# vco1_components.net
KiCad netlist of a schematic drawn in EAGLE
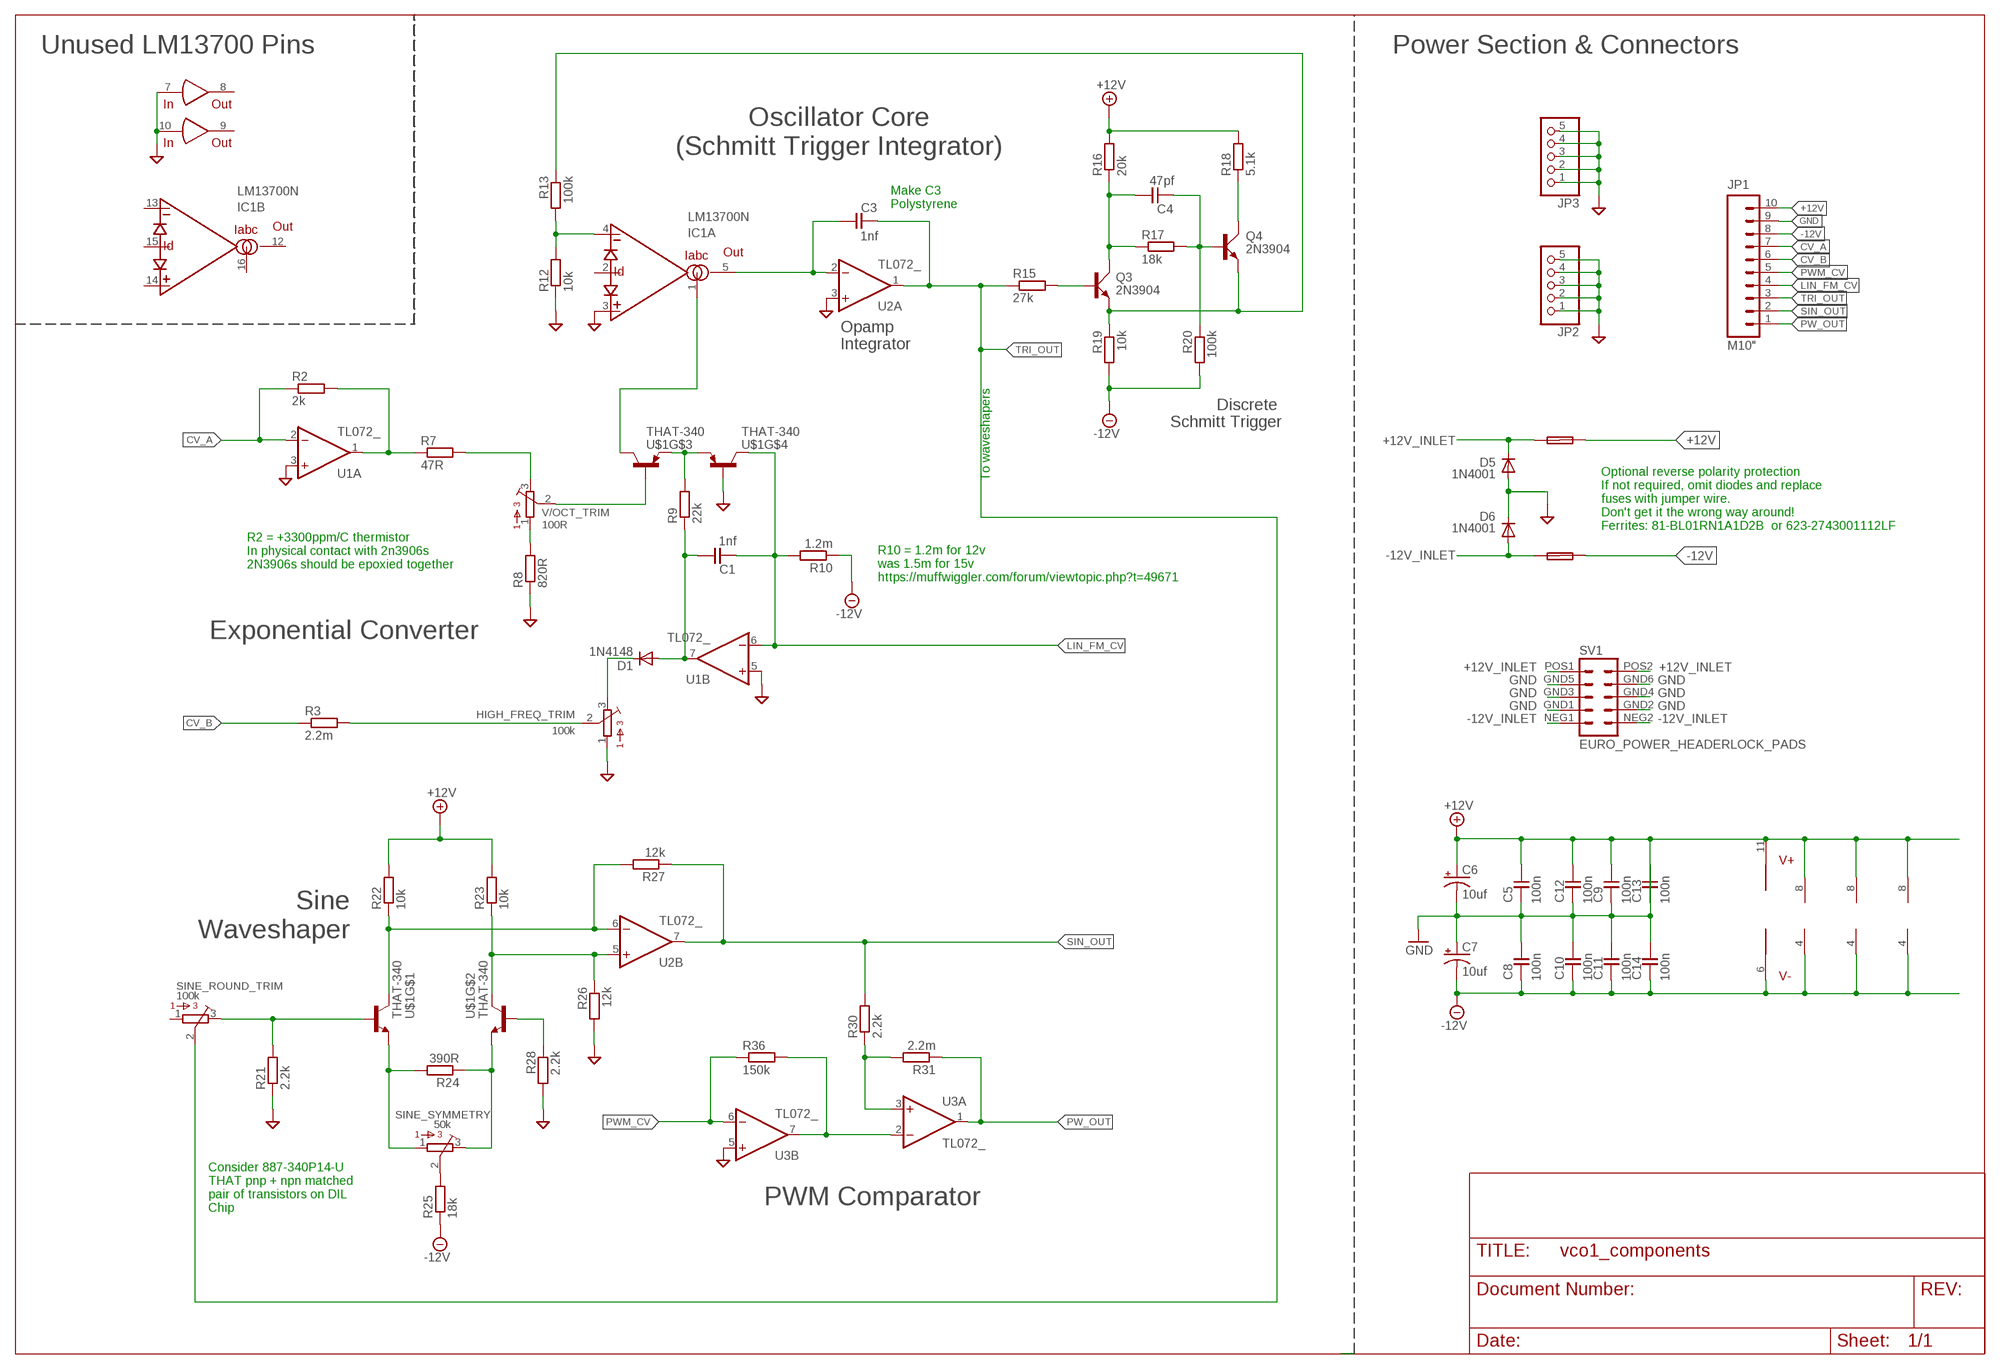
[diagram p0: schematic, sheet 1]

(export (version "E")
  (design (tool "Eeschema 10.0.6"))
  (components
    (comp (ref "C1")
      (value "1nf")
      (footprint "eagle-import:C050-024X044")
      (libsource (lib "eagle-import") (part "C-EU050-024X044"))
    )
    (comp (ref "C3")
      (value "1nf")
      (footprint "eagle-import:C050-024X044")
      (libsource (lib "eagle-import") (part "C-EU050-024X044"))
    )
    (comp (ref "C4")
      (value "47pf")
      (footprint "eagle-import:C050-024X044")
      (libsource (lib "eagle-import") (part "C-EU050-024X044"))
    )
    (comp (ref "C5")
      (value "100n")
      (footprint "eagle-import:C050-024X044")
      (libsource (lib "eagle-import") (part "C-EU050-024X044"))
    )
    (comp (ref "C6")
      (value "10uf")
      (footprint "eagle-import:CPOL-RADIAL-10UF-25V")
      (libsource (lib "eagle-import") (part "CAP_POLPTH2"))
    )
    (comp (ref "C7")
      (value "10uf")
      (footprint "eagle-import:CPOL-RADIAL-10UF-25V")
      (libsource (lib "eagle-import") (part "CAP_POLPTH2"))
    )
    (comp (ref "C8")
      (value "100n")
      (footprint "eagle-import:C050-024X044")
      (libsource (lib "eagle-import") (part "C-EU050-024X044"))
    )
    (comp (ref "C9")
      (value "100n")
      (footprint "eagle-import:C050-024X044")
      (libsource (lib "eagle-import") (part "C-EU050-024X044"))
    )
    (comp (ref "C10")
      (value "100n")
      (footprint "eagle-import:C050-024X044")
      (libsource (lib "eagle-import") (part "C-EU050-024X044"))
    )
    (comp (ref "C11")
      (value "100n")
      (footprint "eagle-import:C050-024X044")
      (libsource (lib "eagle-import") (part "C-EU050-024X044"))
    )
    (comp (ref "C12")
      (value "100n")
      (footprint "eagle-import:C050-024X044")
      (libsource (lib "eagle-import") (part "C-EU050-024X044"))
    )
    (comp (ref "C13")
      (value "100n")
      (footprint "eagle-import:C050-024X044")
      (libsource (lib "eagle-import") (part "C-EU050-024X044"))
    )
    (comp (ref "C14")
      (value "100n")
      (footprint "eagle-import:C050-024X044")
      (libsource (lib "eagle-import") (part "C-EU050-024X044"))
    )
    (comp (ref "D1")
      (value "1N4148")
      (footprint "eagle-import:DO35-7")
      (libsource (lib "eagle-import") (part "SMALL_DIODEDO35-7"))
    )
    (comp (ref "D5")
      (value "1N4001")
      (footprint "eagle-import:DO41-10")
      (libsource (lib "eagle-import") (part "1N4004"))
    )
    (comp (ref "D6")
      (value "1N4001")
      (footprint "eagle-import:DO41-10")
      (libsource (lib "eagle-import") (part "1N4004"))
    )
    (comp (ref "F1")
      (value "FUSE")
      (footprint "eagle-import:C050H075X075")
      (libsource (lib "eagle-import") (part "PTC_FUSEPOLY_FUSE"))
    )
    (comp (ref "F2")
      (value "FUSE")
      (footprint "eagle-import:C050H075X075")
      (libsource (lib "eagle-import") (part "PTC_FUSEPOLY_FUSE"))
    )
    (comp (ref "HIGH_FREQ_TRIM")
      (value "100k")
      (footprint "eagle-import:BOURNS_3362P_TRIMMER")
      (libsource (lib "eagle-import") (part "BOURNS_3362P_TRIMMERP"))
    )
    (comp (ref "IC1")
      (value "LM13700N")
      (footprint "eagle-import:DIL16")
      (libsource (lib "eagle-import") (part "LM13700N"))
    )
    (comp (ref "JP1")
      (value "M10\"")
      (footprint "eagle-import:1X10")
      (libsource (lib "eagle-import") (part "M10{dblquote}"))
    )
    (comp (ref "JP2")
      (value "PINHD-1X55X2MM")
      (footprint "eagle-import:1_05X2MM")
      (libsource (lib "eagle-import") (part "PINHD-1X55X2MM"))
    )
    (comp (ref "JP3")
      (value "PINHD-1X55X2MM")
      (footprint "eagle-import:1_05X2MM")
      (libsource (lib "eagle-import") (part "PINHD-1X55X2MM"))
    )
    (comp (ref "Q3")
      (value "2N3904")
      (footprint "eagle-import:TO92D")
      (libsource (lib "eagle-import") (part "2N3904"))
    )
    (comp (ref "Q4")
      (value "2N3904")
      (footprint "eagle-import:TO92D")
      (libsource (lib "eagle-import") (part "2N3904"))
    )
    (comp (ref "R2")
      (value "2k")
      (footprint "eagle-import:7MM_RESISTOR")
      (libsource (lib "eagle-import") (part "RESISTOR7MM"))
    )
    (comp (ref "R3")
      (value "2.2m")
      (footprint "eagle-import:7MM_RESISTOR")
      (libsource (lib "eagle-import") (part "RESISTOR7MM"))
    )
    (comp (ref "R7")
      (value "47R")
      (footprint "eagle-import:7MM_RESISTOR")
      (libsource (lib "eagle-import") (part "RESISTOR7MM"))
    )
    (comp (ref "R8")
      (value "820R")
      (footprint "eagle-import:7MM_RESISTOR")
      (libsource (lib "eagle-import") (part "RESISTOR7MM"))
    )
    (comp (ref "R9")
      (value "22k")
      (footprint "eagle-import:7MM_RESISTOR")
      (libsource (lib "eagle-import") (part "RESISTOR7MM"))
    )
    (comp (ref "R10")
      (value "1.2m")
      (footprint "eagle-import:7MM_RESISTOR")
      (libsource (lib "eagle-import") (part "RESISTOR7MM"))
    )
    (comp (ref "R12")
      (value "10k")
      (footprint "eagle-import:7MM_RESISTOR")
      (libsource (lib "eagle-import") (part "RESISTOR7MM"))
    )
    (comp (ref "R13")
      (value "100k")
      (footprint "eagle-import:7MM_RESISTOR")
      (libsource (lib "eagle-import") (part "RESISTOR7MM"))
    )
    (comp (ref "R15")
      (value "27k")
      (footprint "eagle-import:7MM_RESISTOR")
      (libsource (lib "eagle-import") (part "RESISTOR7MM"))
    )
    (comp (ref "R16")
      (value "20k")
      (footprint "eagle-import:7MM_RESISTOR")
      (libsource (lib "eagle-import") (part "RESISTOR7MM"))
    )
    (comp (ref "R17")
      (value "18k")
      (footprint "eagle-import:7MM_RESISTOR")
      (libsource (lib "eagle-import") (part "RESISTOR7MM"))
    )
    (comp (ref "R18")
      (value "5.1k")
      (footprint "eagle-import:7MM_RESISTOR")
      (libsource (lib "eagle-import") (part "RESISTOR7MM"))
    )
    (comp (ref "R19")
      (value "10k")
      (footprint "eagle-import:7MM_RESISTOR")
      (libsource (lib "eagle-import") (part "RESISTOR7MM"))
    )
    (comp (ref "R20")
      (value "100k")
      (footprint "eagle-import:7MM_RESISTOR")
      (libsource (lib "eagle-import") (part "RESISTOR7MM"))
    )
    (comp (ref "R21")
      (value "2.2k")
      (footprint "eagle-import:7MM_RESISTOR")
      (libsource (lib "eagle-import") (part "RESISTOR7MM"))
    )
    (comp (ref "R22")
      (value "10k")
      (footprint "eagle-import:7MM_RESISTOR")
      (libsource (lib "eagle-import") (part "RESISTOR7MM"))
    )
    (comp (ref "R23")
      (value "10k")
      (footprint "eagle-import:7MM_RESISTOR")
      (libsource (lib "eagle-import") (part "RESISTOR7MM"))
    )
    (comp (ref "R24")
      (value "390R")
      (footprint "eagle-import:7MM_RESISTOR")
      (libsource (lib "eagle-import") (part "RESISTOR7MM"))
    )
    (comp (ref "R25")
      (value "18k")
      (footprint "eagle-import:7MM_RESISTOR")
      (libsource (lib "eagle-import") (part "RESISTOR7MM"))
    )
    (comp (ref "R26")
      (value "12k")
      (footprint "eagle-import:7MM_RESISTOR")
      (libsource (lib "eagle-import") (part "RESISTOR7MM"))
    )
    (comp (ref "R27")
      (value "12k")
      (footprint "eagle-import:7MM_RESISTOR")
      (libsource (lib "eagle-import") (part "RESISTOR7MM"))
    )
    (comp (ref "R28")
      (value "2.2k")
      (footprint "eagle-import:7MM_RESISTOR")
      (libsource (lib "eagle-import") (part "RESISTOR7MM"))
    )
    (comp (ref "R30")
      (value "2.2k")
      (footprint "eagle-import:7MM_RESISTOR")
      (libsource (lib "eagle-import") (part "RESISTOR7MM"))
    )
    (comp (ref "R31")
      (value "2.2m")
      (footprint "eagle-import:7MM_RESISTOR")
      (libsource (lib "eagle-import") (part "RESISTOR7MM"))
    )
    (comp (ref "R36")
      (value "150k")
      (footprint "eagle-import:7MM_RESISTOR")
      (libsource (lib "eagle-import") (part "RESISTOR7MM"))
    )
    (comp (ref "SINE_ROUND_TRIM")
      (value "100k")
      (footprint "eagle-import:BOURNS_3362P_TRIMMER")
      (libsource (lib "eagle-import") (part "BOURNS_3362P_TRIMMERP"))
    )
    (comp (ref "SINE_SYMMETRY")
      (value "50k")
      (footprint "eagle-import:BOURNS_3362P_TRIMMER")
      (libsource (lib "eagle-import") (part "BOURNS_3362P_TRIMMERP"))
    )
    (comp (ref "SV1")
      (value "EURO_POWER_HEADERLOCK_PADS")
      (footprint "eagle-import:EURO_PWR_HEADER_LOCK")
      (libsource (lib "eagle-import") (part "EURO_POWER_HEADERLOCK_PADS"))
    )
    (comp (ref "U$1")
      (value "THAT-340")
      (footprint "eagle-import:DIL14")
      (libsource (lib "eagle-import") (part "THAT-340THRUHOLE"))
    )
    (comp (ref "U1")
      (value "TL072_")
      (footprint "eagle-import:DIL08")
      (libsource (lib "eagle-import") (part "TL072_"))
    )
    (comp (ref "U2")
      (value "TL072_")
      (footprint "eagle-import:DIL08")
      (libsource (lib "eagle-import") (part "TL072_"))
    )
    (comp (ref "U3")
      (value "TL072_")
      (footprint "eagle-import:DIL08")
      (libsource (lib "eagle-import") (part "TL072_"))
    )
    (comp (ref "V/OCT_TRIM")
      (value "100R")
      (footprint "eagle-import:BOURNS_3362P_TRIMMER")
      (libsource (lib "eagle-import") (part "BOURNS_3362P_TRIMMERP"))
    )
  )
  (nets
    (net (code "1") (name "+12V") (class "Default")
      (node (ref "C12") (pin "1") (pinfunction "1_1") (pintype "passive"))
      (node (ref "C13") (pin "2") (pinfunction "2_2") (pintype "passive"))
      (node (ref "C5") (pin "1") (pinfunction "1_1") (pintype "passive"))
      (node (ref "C6") (pin "1") (pinfunction "+_1") (pintype "passive"))
      (node (ref "C9") (pin "1") (pinfunction "1_1") (pintype "passive"))
      (node (ref "F1") (pin "2") (pinfunction "P$2_2") (pintype "bidirectional"))
      (node (ref "IC1") (pin "11") (pinfunction "V+_11") (pintype "bidirectional"))
      (node (ref "JP1") (pin "10") (pinfunction "10_10") (pintype "passive"))
      (node (ref "R16") (pin "2") (pinfunction "2_2") (pintype "passive"))
      (node (ref "R18") (pin "2") (pinfunction "2_2") (pintype "passive"))
      (node (ref "R22") (pin "2") (pinfunction "2_2") (pintype "passive"))
      (node (ref "R23") (pin "2") (pinfunction "2_2") (pintype "passive"))
      (node (ref "U1") (pin "8") (pinfunction "V+_8") (pintype "power_in"))
      (node (ref "U2") (pin "8") (pinfunction "V+_8") (pintype "power_in"))
      (node (ref "U3") (pin "8") (pinfunction "V+_8") (pintype "power_in"))
    )
    (net (code "2") (name "-12V") (class "Default")
      (node (ref "C10") (pin "2") (pinfunction "2_2") (pintype "passive"))
      (node (ref "C11") (pin "2") (pinfunction "2_2") (pintype "passive"))
      (node (ref "C14") (pin "2") (pinfunction "2_2") (pintype "passive"))
      (node (ref "C7") (pin "2") (pinfunction "-_2") (pintype "passive"))
      (node (ref "C8") (pin "2") (pinfunction "2_2") (pintype "passive"))
      (node (ref "F2") (pin "2") (pinfunction "P$2_2") (pintype "bidirectional"))
      (node (ref "IC1") (pin "6") (pinfunction "V-_6") (pintype "bidirectional"))
      (node (ref "JP1") (pin "8") (pinfunction "8_8") (pintype "passive"))
      (node (ref "R10") (pin "1") (pinfunction "1_1") (pintype "passive"))
      (node (ref "R19") (pin "2") (pinfunction "2_2") (pintype "passive"))
      (node (ref "R20") (pin "2") (pinfunction "2_2") (pintype "passive"))
      (node (ref "R25") (pin "1") (pinfunction "1_1") (pintype "passive"))
      (node (ref "U1") (pin "4") (pinfunction "V-_4") (pintype "power_in"))
      (node (ref "U2") (pin "4") (pinfunction "V-_4") (pintype "power_in"))
      (node (ref "U3") (pin "4") (pinfunction "V-_4") (pintype "power_in"))
    )
    (net (code "3") (name "/+12V_INLET") (class "Default")
      (node (ref "D5") (pin "C") (pinfunction "C_C") (pintype "passive"))
      (node (ref "F1") (pin "1") (pinfunction "P$1_1") (pintype "bidirectional"))
      (node (ref "SV1") (pin "POS1") (pinfunction "10_POS1") (pintype "passive"))
      (node (ref "SV1") (pin "POS2") (pinfunction "9_POS2") (pintype "passive"))
    )
    (net (code "4") (name "/-12V_INLET") (class "Default")
      (node (ref "D6") (pin "A") (pinfunction "A_A") (pintype "passive"))
      (node (ref "F2") (pin "1") (pinfunction "P$1_1") (pintype "bidirectional"))
      (node (ref "SV1") (pin "NEG1") (pinfunction "2_NEG1") (pintype "passive"))
      (node (ref "SV1") (pin "NEG2") (pinfunction "1_NEG2") (pintype "passive"))
    )
    (net (code "5") (name "CV_A") (class "Default")
      (node (ref "JP1") (pin "7") (pinfunction "7_7") (pintype "passive"))
      (node (ref "R2") (pin "1") (pinfunction "1_1") (pintype "passive"))
      (node (ref "U1") (pin "2") (pinfunction "-IN_2") (pintype "input"))
    )
    (net (code "6") (name "CV_B") (class "Default")
      (node (ref "JP1") (pin "6") (pinfunction "6_6") (pintype "passive"))
      (node (ref "R3") (pin "1") (pinfunction "1_1") (pintype "passive"))
    )
    (net (code "7") (name "GND") (class "Default")
      (node (ref "C10") (pin "1") (pinfunction "1_1") (pintype "passive"))
      (node (ref "C11") (pin "1") (pinfunction "1_1") (pintype "passive"))
      (node (ref "C12") (pin "2") (pinfunction "2_2") (pintype "passive"))
      (node (ref "C13") (pin "1") (pinfunction "1_1") (pintype "passive"))
      (node (ref "C14") (pin "1") (pinfunction "1_1") (pintype "passive"))
      (node (ref "C5") (pin "2") (pinfunction "2_2") (pintype "passive"))
      (node (ref "C6") (pin "2") (pinfunction "-_2") (pintype "passive"))
      (node (ref "C7") (pin "1") (pinfunction "+_1") (pintype "passive"))
      (node (ref "C8") (pin "1") (pinfunction "1_1") (pintype "passive"))
      (node (ref "C9") (pin "2") (pinfunction "2_2") (pintype "passive"))
      (node (ref "D5") (pin "A") (pinfunction "A_A") (pintype "passive"))
      (node (ref "D6") (pin "C") (pinfunction "C_C") (pintype "passive"))
      (node (ref "HIGH_FREQ_TRIM") (pin "1") (pinfunction "1_1") (pintype "passive"))
      (node (ref "IC1") (pin "10") (pinfunction "IN_10") (pintype "bidirectional"))
      (node (ref "IC1") (pin "3") (pinfunction "+IN_3") (pintype "bidirectional"))
      (node (ref "IC1") (pin "7") (pinfunction "IN_7") (pintype "bidirectional"))
      (node (ref "JP1") (pin "9") (pinfunction "9_9") (pintype "passive"))
      (node (ref "JP2") (pin "1") (pinfunction "1_1") (pintype "passive"))
      (node (ref "JP2") (pin "2") (pinfunction "2_2") (pintype "passive"))
      (node (ref "JP2") (pin "3") (pinfunction "3_3") (pintype "passive"))
      (node (ref "JP2") (pin "4") (pinfunction "4_4") (pintype "passive"))
      (node (ref "JP2") (pin "5") (pinfunction "5_5") (pintype "passive"))
      (node (ref "JP3") (pin "1") (pinfunction "1_1") (pintype "passive"))
      (node (ref "JP3") (pin "2") (pinfunction "2_2") (pintype "passive"))
      (node (ref "JP3") (pin "3") (pinfunction "3_3") (pintype "passive"))
      (node (ref "JP3") (pin "4") (pinfunction "4_4") (pintype "passive"))
      (node (ref "JP3") (pin "5") (pinfunction "5_5") (pintype "passive"))
      (node (ref "R12") (pin "1") (pinfunction "1_1") (pintype "passive"))
      (node (ref "R21") (pin "1") (pinfunction "1_1") (pintype "passive"))
      (node (ref "R26") (pin "2") (pinfunction "2_2") (pintype "passive"))
      (node (ref "R28") (pin "2") (pinfunction "2_2") (pintype "passive"))
      (node (ref "R8") (pin "1") (pinfunction "1_1") (pintype "passive"))
      (node (ref "SV1") (pin "GND1") (pinfunction "4_GND1") (pintype "passive"))
      (node (ref "SV1") (pin "GND2") (pinfunction "3_GND2") (pintype "passive"))
      (node (ref "SV1") (pin "GND3") (pinfunction "6_GND3") (pintype "passive"))
      (node (ref "SV1") (pin "GND4") (pinfunction "5_GND4") (pintype "passive"))
      (node (ref "SV1") (pin "GND5") (pinfunction "8_GND5") (pintype "passive"))
      (node (ref "SV1") (pin "GND6") (pinfunction "7_GND6") (pintype "passive"))
      (node (ref "U$1") (pin "9") (pinfunction "B_9") (pintype "passive"))
      (node (ref "U1") (pin "3") (pinfunction "+IN_3") (pintype "input"))
      (node (ref "U1") (pin "5") (pinfunction "+IN_5") (pintype "input"))
      (node (ref "U2") (pin "3") (pinfunction "+IN_3") (pintype "input"))
      (node (ref "U3") (pin "5") (pinfunction "+IN_5") (pintype "input"))
    )
    (net (code "8") (name "LIN_FM_CV") (class "Default")
      (node (ref "C1") (pin "2") (pinfunction "2_2") (pintype "passive"))
      (node (ref "JP1") (pin "4") (pinfunction "4_4") (pintype "passive"))
      (node (ref "R10") (pin "2") (pinfunction "2_2") (pintype "passive"))
      (node (ref "U$1") (pin "8") (pinfunction "C_8") (pintype "passive"))
      (node (ref "U1") (pin "6") (pinfunction "-IN_6") (pintype "input"))
    )
    (net (code "9") (name "Net-(C4-Pad1)") (class "Default")
      (node (ref "C4") (pin "1") (pinfunction "1_1") (pintype "passive"))
      (node (ref "Q3") (pin "C") (pinfunction "C_C") (pintype "passive"))
      (node (ref "R16") (pin "1") (pinfunction "1_1") (pintype "passive"))
      (node (ref "R17") (pin "1") (pinfunction "1_1") (pintype "passive"))
    )
    (net (code "10") (name "Net-(C4-Pad2)") (class "Default")
      (node (ref "C4") (pin "2") (pinfunction "2_2") (pintype "passive"))
      (node (ref "Q4") (pin "B") (pinfunction "B_B") (pintype "passive"))
      (node (ref "R17") (pin "2") (pinfunction "2_2") (pintype "passive"))
      (node (ref "R20") (pin "1") (pinfunction "1_1") (pintype "passive"))
    )
    (net (code "11") (name "Net-(D1-PadC)") (class "Default")
      (node (ref "D1") (pin "C") (pinfunction "C_C") (pintype "passive"))
      (node (ref "HIGH_FREQ_TRIM") (pin "3") (pinfunction "3_3") (pintype "passive"))
    )
    (net (code "12") (name "Net-(HIGH_FREQ_TRIM-Pad2)") (class "Default")
      (node (ref "HIGH_FREQ_TRIM") (pin "2") (pinfunction "2_2") (pintype "passive"))
      (node (ref "R3") (pin "2") (pinfunction "2_2") (pintype "passive"))
    )
    (net (code "13") (name "Net-(IC1A--IN)") (class "Default")
      (node (ref "IC1") (pin "4") (pinfunction "-IN_4") (pintype "bidirectional"))
      (node (ref "R12") (pin "2") (pinfunction "2_2") (pintype "passive"))
      (node (ref "R13") (pin "2") (pinfunction "2_2") (pintype "passive"))
    )
    (net (code "14") (name "Net-(IC1A-IABC)") (class "Default")
      (node (ref "IC1") (pin "1") (pinfunction "IABC_1") (pintype "bidirectional"))
      (node (ref "U$1") (pin "7") (pinfunction "C_7") (pintype "passive"))
    )
    (net (code "15") (name "Net-(IC1A-OUT)") (class "Default")
      (node (ref "C3") (pin "1") (pinfunction "1_1") (pintype "passive"))
      (node (ref "IC1") (pin "5") (pinfunction "OUT_5") (pintype "bidirectional"))
      (node (ref "U2") (pin "2") (pinfunction "-IN_2") (pintype "input"))
    )
    (net (code "16") (name "Net-(Q3-PadB)") (class "Default")
      (node (ref "Q3") (pin "B") (pinfunction "B_B") (pintype "passive"))
      (node (ref "R15") (pin "2") (pinfunction "2_2") (pintype "passive"))
    )
    (net (code "17") (name "Net-(Q3-PadE)") (class "Default")
      (node (ref "Q3") (pin "E") (pinfunction "E_E") (pintype "passive"))
      (node (ref "Q4") (pin "E") (pinfunction "E_E") (pintype "passive"))
      (node (ref "R13") (pin "1") (pinfunction "1_1") (pintype "passive"))
      (node (ref "R19") (pin "1") (pinfunction "1_1") (pintype "passive"))
    )
    (net (code "18") (name "Net-(Q4-PadC)") (class "Default")
      (node (ref "Q4") (pin "C") (pinfunction "C_C") (pintype "passive"))
      (node (ref "R18") (pin "1") (pinfunction "1_1") (pintype "passive"))
    )
    (net (code "19") (name "Net-(R7-Pad2)") (class "Default")
      (node (ref "R7") (pin "2") (pinfunction "2_2") (pintype "passive"))
      (node (ref "V/OCT_TRIM") (pin "3") (pinfunction "3_3") (pintype "passive"))
    )
    (net (code "20") (name "Net-(R8-Pad2)") (class "Default")
      (node (ref "R8") (pin "2") (pinfunction "2_2") (pintype "passive"))
      (node (ref "V/OCT_TRIM") (pin "1") (pinfunction "1_1") (pintype "passive"))
    )
    (net (code "21") (name "Net-(R25-Pad2)") (class "Default")
      (node (ref "R25") (pin "2") (pinfunction "2_2") (pintype "passive"))
      (node (ref "SINE_SYMMETRY") (pin "2") (pinfunction "2_2") (pintype "passive"))
    )
    (net (code "22") (name "Net-(U$1A-B)") (class "Default")
      (node (ref "R21") (pin "2") (pinfunction "2_2") (pintype "passive"))
      (node (ref "SINE_ROUND_TRIM") (pin "3") (pinfunction "3_3") (pintype "passive"))
      (node (ref "U$1") (pin "2") (pinfunction "B_2") (pintype "passive"))
    )
    (net (code "23") (name "Net-(U$1A-C)") (class "Default")
      (node (ref "R22") (pin "1") (pinfunction "1_1") (pintype "passive"))
      (node (ref "R27") (pin "2") (pinfunction "2_2") (pintype "passive"))
      (node (ref "U$1") (pin "1") (pinfunction "C_1") (pintype "passive"))
      (node (ref "U2") (pin "6") (pinfunction "-IN_6") (pintype "input"))
    )
    (net (code "24") (name "Net-(U$1A-E)") (class "Default")
      (node (ref "R24") (pin "2") (pinfunction "2_2") (pintype "passive"))
      (node (ref "SINE_SYMMETRY") (pin "1") (pinfunction "1_1") (pintype "passive"))
      (node (ref "U$1") (pin "3") (pinfunction "E_3") (pintype "passive"))
    )
    (net (code "25") (name "Net-(U$1B-B)") (class "Default")
      (node (ref "R28") (pin "1") (pinfunction "1_1") (pintype "passive"))
      (node (ref "U$1") (pin "13") (pinfunction "B_13") (pintype "passive"))
    )
    (net (code "26") (name "Net-(U$1B-C)") (class "Default")
      (node (ref "R23") (pin "1") (pinfunction "1_1") (pintype "passive"))
      (node (ref "R26") (pin "1") (pinfunction "1_1") (pintype "passive"))
      (node (ref "U$1") (pin "14") (pinfunction "C_14") (pintype "passive"))
      (node (ref "U2") (pin "5") (pinfunction "+IN_5") (pintype "input"))
    )
    (net (code "27") (name "Net-(U$1B-E)") (class "Default")
      (node (ref "R24") (pin "1") (pinfunction "1_1") (pintype "passive"))
      (node (ref "SINE_SYMMETRY") (pin "3") (pinfunction "3_3") (pintype "passive"))
      (node (ref "U$1") (pin "12") (pinfunction "E_12") (pintype "passive"))
    )
    (net (code "28") (name "Net-(U$1C-B)") (class "Default")
      (node (ref "U$1") (pin "6") (pinfunction "B_6") (pintype "passive"))
      (node (ref "V/OCT_TRIM") (pin "2") (pinfunction "2_2") (pintype "passive"))
    )
    (net (code "29") (name "Net-(U$1C-E)") (class "Default")
      (node (ref "R9") (pin "2") (pinfunction "2_2") (pintype "passive"))
      (node (ref "U$1") (pin "10") (pinfunction "E_10") (pintype "passive"))
      (node (ref "U$1") (pin "5") (pinfunction "E_5") (pintype "passive"))
    )
    (net (code "30") (name "Net-(U1A-OUT)") (class "Default")
      (node (ref "R2") (pin "2") (pinfunction "2_2") (pintype "passive"))
      (node (ref "R7") (pin "1") (pinfunction "1_1") (pintype "passive"))
      (node (ref "U1") (pin "1") (pinfunction "OUT_1") (pintype "output"))
    )
    (net (code "31") (name "Net-(U1B-OUT)") (class "Default")
      (node (ref "C1") (pin "1") (pinfunction "1_1") (pintype "passive"))
      (node (ref "D1") (pin "A") (pinfunction "A_A") (pintype "passive"))
      (node (ref "R9") (pin "1") (pinfunction "1_1") (pintype "passive"))
      (node (ref "U1") (pin "7") (pinfunction "OUT_7") (pintype "output"))
    )
    (net (code "32") (name "Net-(U3A-+IN)") (class "Default")
      (node (ref "R30") (pin "1") (pinfunction "1_1") (pintype "passive"))
      (node (ref "R31") (pin "2") (pinfunction "2_2") (pintype "passive"))
      (node (ref "U3") (pin "3") (pinfunction "+IN_3") (pintype "input"))
    )
    (net (code "33") (name "Net-(U3A--IN)") (class "Default")
      (node (ref "R36") (pin "2") (pinfunction "2_2") (pintype "passive"))
      (node (ref "U3") (pin "2") (pinfunction "-IN_2") (pintype "input"))
      (node (ref "U3") (pin "7") (pinfunction "OUT_7") (pintype "output"))
    )
    (net (code "34") (name "PWM_CV") (class "Default")
      (node (ref "JP1") (pin "5") (pinfunction "5_5") (pintype "passive"))
      (node (ref "R36") (pin "1") (pinfunction "1_1") (pintype "passive"))
      (node (ref "U3") (pin "6") (pinfunction "-IN_6") (pintype "input"))
    )
    (net (code "35") (name "PW_OUT") (class "Default")
      (node (ref "JP1") (pin "1") (pinfunction "1_1") (pintype "passive"))
      (node (ref "R31") (pin "1") (pinfunction "1_1") (pintype "passive"))
      (node (ref "U3") (pin "1") (pinfunction "OUT_1") (pintype "output"))
    )
    (net (code "36") (name "SIN_OUT") (class "Default")
      (node (ref "JP1") (pin "2") (pinfunction "2_2") (pintype "passive"))
      (node (ref "R27") (pin "1") (pinfunction "1_1") (pintype "passive"))
      (node (ref "R30") (pin "2") (pinfunction "2_2") (pintype "passive"))
      (node (ref "U2") (pin "7") (pinfunction "OUT_7") (pintype "output"))
    )
    (net (code "37") (name "TRI_OUT") (class "Default")
      (node (ref "C3") (pin "2") (pinfunction "2_2") (pintype "passive"))
      (node (ref "JP1") (pin "3") (pinfunction "3_3") (pintype "passive"))
      (node (ref "R15") (pin "1") (pinfunction "1_1") (pintype "passive"))
      (node (ref "SINE_ROUND_TRIM") (pin "2") (pinfunction "2_2") (pintype "passive"))
      (node (ref "U2") (pin "1") (pinfunction "OUT_1") (pintype "output"))
    )
    (net (code "38") (name "unconnected-(IC1A-ID-Pad2)") (class "Default")
      (node (ref "IC1") (pin "2") (pinfunction "ID_2") (pintype "bidirectional"))
    )
    (net (code "39") (name "unconnected-(IC1B-+IN-Pad14)") (class "Default")
      (node (ref "IC1") (pin "14") (pinfunction "+IN_14") (pintype "bidirectional"))
    )
    (net (code "40") (name "unconnected-(IC1B--IN-Pad13)") (class "Default")
      (node (ref "IC1") (pin "13") (pinfunction "-IN_13") (pintype "bidirectional"))
    )
    (net (code "41") (name "unconnected-(IC1B-IABC-Pad16)") (class "Default")
      (node (ref "IC1") (pin "16") (pinfunction "IABC_16") (pintype "bidirectional"))
    )
    (net (code "42") (name "unconnected-(IC1B-ID-Pad15)") (class "Default")
      (node (ref "IC1") (pin "15") (pinfunction "ID_15") (pintype "bidirectional"))
    )
    (net (code "43") (name "unconnected-(IC1B-OUT-Pad12)") (class "Default")
      (node (ref "IC1") (pin "12") (pinfunction "OUT_12") (pintype "bidirectional"))
    )
    (net (code "44") (name "unconnected-(IC1C-OUT-Pad8)") (class "Default")
      (node (ref "IC1") (pin "8") (pinfunction "OUT_8") (pintype "bidirectional"))
    )
    (net (code "45") (name "unconnected-(IC1D-OUT-Pad9)") (class "Default")
      (node (ref "IC1") (pin "9") (pinfunction "OUT_9") (pintype "bidirectional"))
    )
    (net (code "46") (name "unconnected-(SINE_ROUND_TRIM-Pad1)") (class "Default")
      (node (ref "SINE_ROUND_TRIM") (pin "1") (pinfunction "1_1") (pintype "passive"))
    )
  )
)
